# BL654.net
KiCad netlist of a schematic drawn in Altium Designer
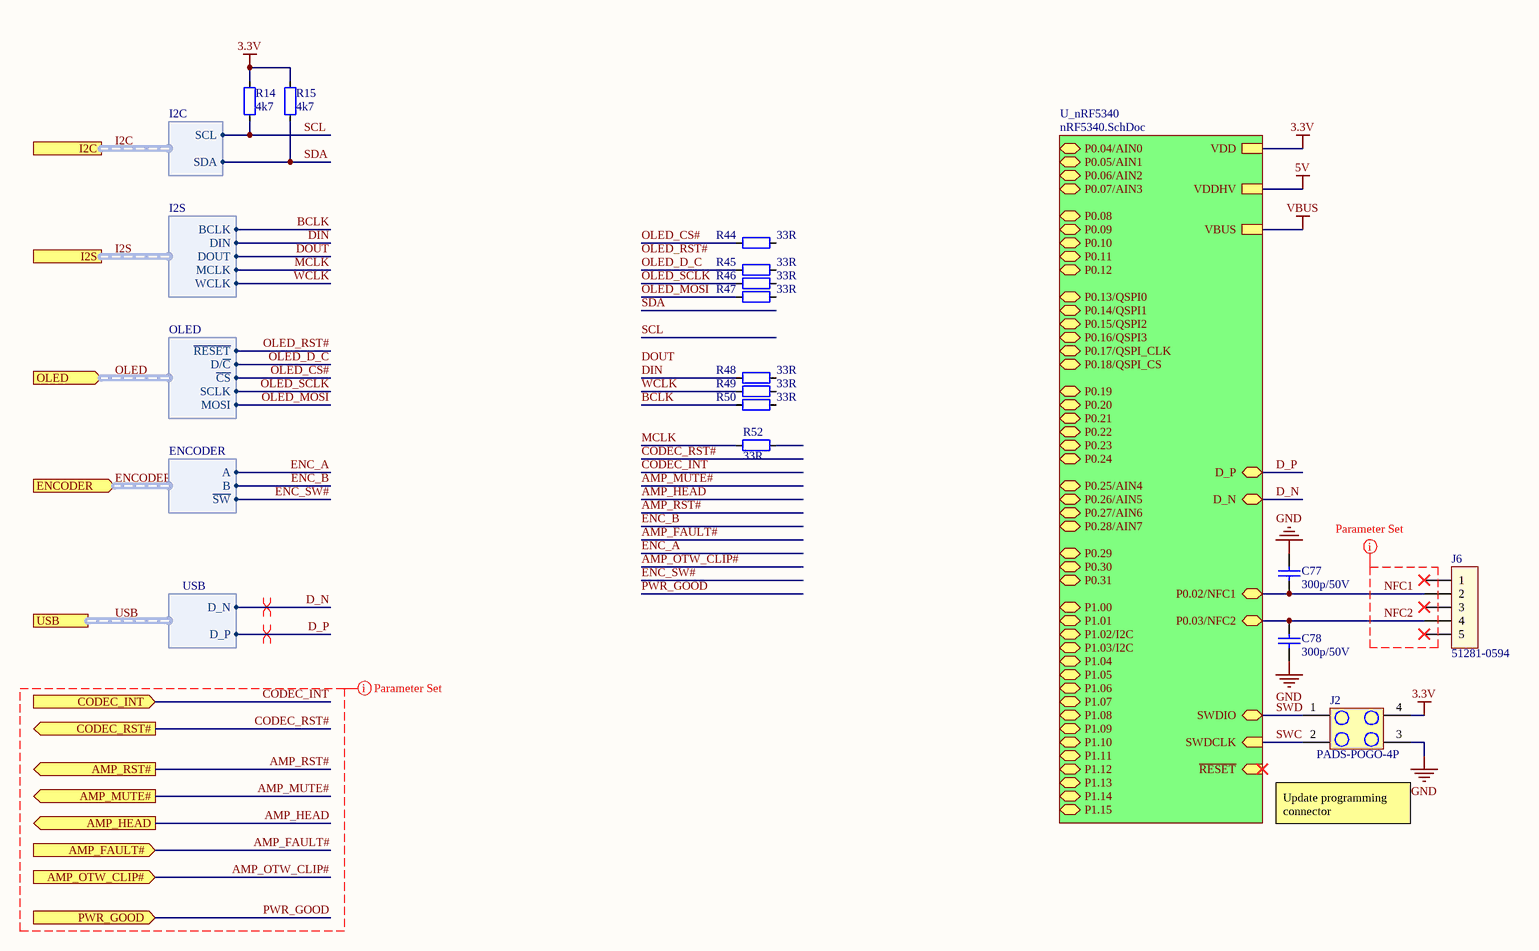
[diagram p0: BL654.SchDoc]

(export (version "E")
  (design (tool "Eeschema 10.0.6"))
  (components
    (comp (ref "C77")
      (value "300p/50V")
      (footprint "C0402")
      (fields (field (name "VOLTAGE") "50V") (field (name "TOLERANCE") "10%"))
      (libsource (lib "dk_capacitors") (part "300p 50V X7R 0402"))
    )
    (comp (ref "C78")
      (value "300p/50V")
      (footprint "C0402")
      (fields (field (name "VOLTAGE") "50V") (field (name "TOLERANCE") "10%"))
      (libsource (lib "dk_capacitors") (part "300p 50V X7R 0402"))
    )
    (comp (ref "J2")
      (value "PADS-POGO-4P")
      (footprint "PADS-POGO-4P")
      (description "Pads for 4 pin programming pogo to connect to")
      (libsource (lib "dk_connectors") (part "PADS-POGO-4P"))
    )
    (comp (ref "J6")
      (value "51281-0594")
      (footprint "51281-0594")
      (description "FFC & FPC Connectors 0.5 FPC Non-ZIF 5Ckt Dual Contact")
      (libsource (lib "dk_connectors") (part "51281-0594"))
    )
    (comp (ref "R14")
      (value "4k7")
      (footprint "R0402")
      (fields (field (name "TOLERANCE") "1%") (field (name "VOLTAGE") "50V"))
      (libsource (lib "dk_resistors") (part "4k7 63mW 50V 0402"))
    )
    (comp (ref "R15")
      (value "4k7")
      (footprint "R0402")
      (fields (field (name "TOLERANCE") "1%") (field (name "VOLTAGE") "50V"))
      (libsource (lib "dk_resistors") (part "4k7 63mW 50V 0402"))
    )
    (comp (ref "R44")
      (value "33R")
      (footprint "R0402")
      (fields (field (name "TOLERANCE") "5%") (field (name "VOLTAGE") "50V"))
      (libsource (lib "dk_resistors") (part "33R 63mW 50V 0402"))
    )
    (comp (ref "R45")
      (value "33R")
      (footprint "R0402")
      (fields (field (name "TOLERANCE") "5%") (field (name "VOLTAGE") "50V"))
      (libsource (lib "dk_resistors") (part "33R 63mW 50V 0402"))
    )
    (comp (ref "R46")
      (value "33R")
      (footprint "R0402")
      (fields (field (name "TOLERANCE") "5%") (field (name "VOLTAGE") "50V"))
      (libsource (lib "dk_resistors") (part "33R 63mW 50V 0402"))
    )
    (comp (ref "R47")
      (value "33R")
      (footprint "R0402")
      (fields (field (name "TOLERANCE") "5%") (field (name "VOLTAGE") "50V"))
      (libsource (lib "dk_resistors") (part "33R 63mW 50V 0402"))
    )
    (comp (ref "R48")
      (value "33R")
      (footprint "R0402")
      (fields (field (name "TOLERANCE") "5%") (field (name "VOLTAGE") "50V"))
      (libsource (lib "dk_resistors") (part "33R 63mW 50V 0402"))
    )
    (comp (ref "R49")
      (value "33R")
      (footprint "R0402")
      (fields (field (name "TOLERANCE") "5%") (field (name "VOLTAGE") "50V"))
      (libsource (lib "dk_resistors") (part "33R 63mW 50V 0402"))
    )
    (comp (ref "R50")
      (value "33R")
      (footprint "R0402")
      (fields (field (name "TOLERANCE") "5%") (field (name "VOLTAGE") "50V"))
      (libsource (lib "dk_resistors") (part "33R 63mW 50V 0402"))
    )
    (comp (ref "R52")
      (value "33R")
      (footprint "R0402")
      (fields (field (name "TOLERANCE") "5%") (field (name "VOLTAGE") "50V"))
      (libsource (lib "dk_resistors") (part "33R 63mW 50V 0402"))
    )
  )
  (nets
    (net (code "11") (name "/BCLK") (class "Default")
      (node (ref "R50") (pin "1") (pinfunction "1_1") (pintype "passive"))
    )
    (net (code "14") (name "/DIN") (class "Default")
      (node (ref "R48") (pin "1") (pinfunction "1_1") (pintype "passive"))
    )
    (net (code "24") (name "/MCLK") (class "Default")
      (node (ref "R52") (pin "1") (pinfunction "1_1") (pintype "passive"))
    )
    (net (code "25") (name "/NFC1") (class "Default")
      (node (ref "C77") (pin "1") (pinfunction "1_1") (pintype "passive"))
      (node (ref "J6") (pin "2") (pinfunction "2_2") (pintype "passive"))
    )
    (net (code "26") (name "/NFC2") (class "Default")
      (node (ref "C78") (pin "2") (pinfunction "2_2") (pintype "passive"))
      (node (ref "J6") (pin "4") (pinfunction "4_4") (pintype "passive"))
    )
    (net (code "27") (name "/OLED_CS#") (class "Default")
      (node (ref "R44") (pin "1") (pinfunction "1_1") (pintype "passive"))
    )
    (net (code "28") (name "/OLED_D_C") (class "Default")
      (node (ref "R45") (pin "1") (pinfunction "1_1") (pintype "passive"))
    )
    (net (code "29") (name "/OLED_MOSI") (class "Default")
      (node (ref "R47") (pin "1") (pinfunction "1_1") (pintype "passive"))
    )
    (net (code "31") (name "/OLED_SCLK") (class "Default")
      (node (ref "R46") (pin "1") (pinfunction "1_1") (pintype "passive"))
    )
    (net (code "78") (name "/SCL") (class "Default")
      (node (ref "R14") (pin "1") (pinfunction "1_1") (pintype "passive"))
    )
    (net (code "79") (name "/SDA") (class "Default")
      (node (ref "R15") (pin "1") (pinfunction "1_1") (pintype "passive"))
    )
    (net (code "80") (name "/SWC") (class "Default") (node (ref "J2") (pin "2") (pintype "passive")))
    (net (code "81") (name "/SWD") (class "Default") (node (ref "J2") (pin "1") (pintype "passive")))
    (net (code "83") (name "/WCLK") (class "Default")
      (node (ref "R49") (pin "1") (pinfunction "1_1") (pintype "passive"))
    )
    (net (code "85") (name "3.3V") (class "Default")
      (node (ref "J2") (pin "4") (pintype "passive"))
      (node (ref "R14") (pin "2") (pinfunction "2_2") (pintype "passive"))
      (node (ref "R15") (pin "2") (pinfunction "2_2") (pintype "passive"))
    )
    (net (code "87") (name "GND") (class "Default")
      (node (ref "C77") (pin "2") (pinfunction "2_2") (pintype "passive"))
      (node (ref "C78") (pin "1") (pinfunction "1_1") (pintype "passive"))
      (node (ref "J2") (pin "3") (pintype "passive"))
    )
    (net (code "89") (name "unconnected-(J6-Pad1)") (class "Default")
      (node (ref "J6") (pin "1") (pinfunction "1_1") (pintype "passive+no_connect"))
    )
    (net (code "90") (name "unconnected-(J6-Pad3)") (class "Default")
      (node (ref "J6") (pin "3") (pinfunction "3_3") (pintype "passive+no_connect"))
    )
    (net (code "91") (name "unconnected-(J6-Pad5)") (class "Default")
      (node (ref "J6") (pin "5") (pinfunction "5_5") (pintype "passive+no_connect"))
    )
    (net (code "92") (name "unconnected-(R44-Pad2)") (class "Default")
      (node (ref "R44") (pin "2") (pinfunction "2_2") (pintype "passive"))
    )
    (net (code "93") (name "unconnected-(R45-Pad2)") (class "Default")
      (node (ref "R45") (pin "2") (pinfunction "2_2") (pintype "passive"))
    )
    (net (code "94") (name "unconnected-(R46-Pad2)") (class "Default")
      (node (ref "R46") (pin "2") (pinfunction "2_2") (pintype "passive"))
    )
    (net (code "95") (name "unconnected-(R47-Pad2)") (class "Default")
      (node (ref "R47") (pin "2") (pinfunction "2_2") (pintype "passive"))
    )
    (net (code "96") (name "unconnected-(R48-Pad2)") (class "Default")
      (node (ref "R48") (pin "2") (pinfunction "2_2") (pintype "passive"))
    )
    (net (code "97") (name "unconnected-(R49-Pad2)") (class "Default")
      (node (ref "R49") (pin "2") (pinfunction "2_2") (pintype "passive"))
    )
    (net (code "98") (name "unconnected-(R50-Pad2)") (class "Default")
      (node (ref "R50") (pin "2") (pinfunction "2_2") (pintype "passive"))
    )
    (net (code "99") (name "unconnected-(R52-Pad2)") (class "Default")
      (node (ref "R52") (pin "2") (pinfunction "2_2") (pintype "passive"))
    )
  )
)
